# EQ_2.net
KiCad netlist of a schematic drawn in EAGLE
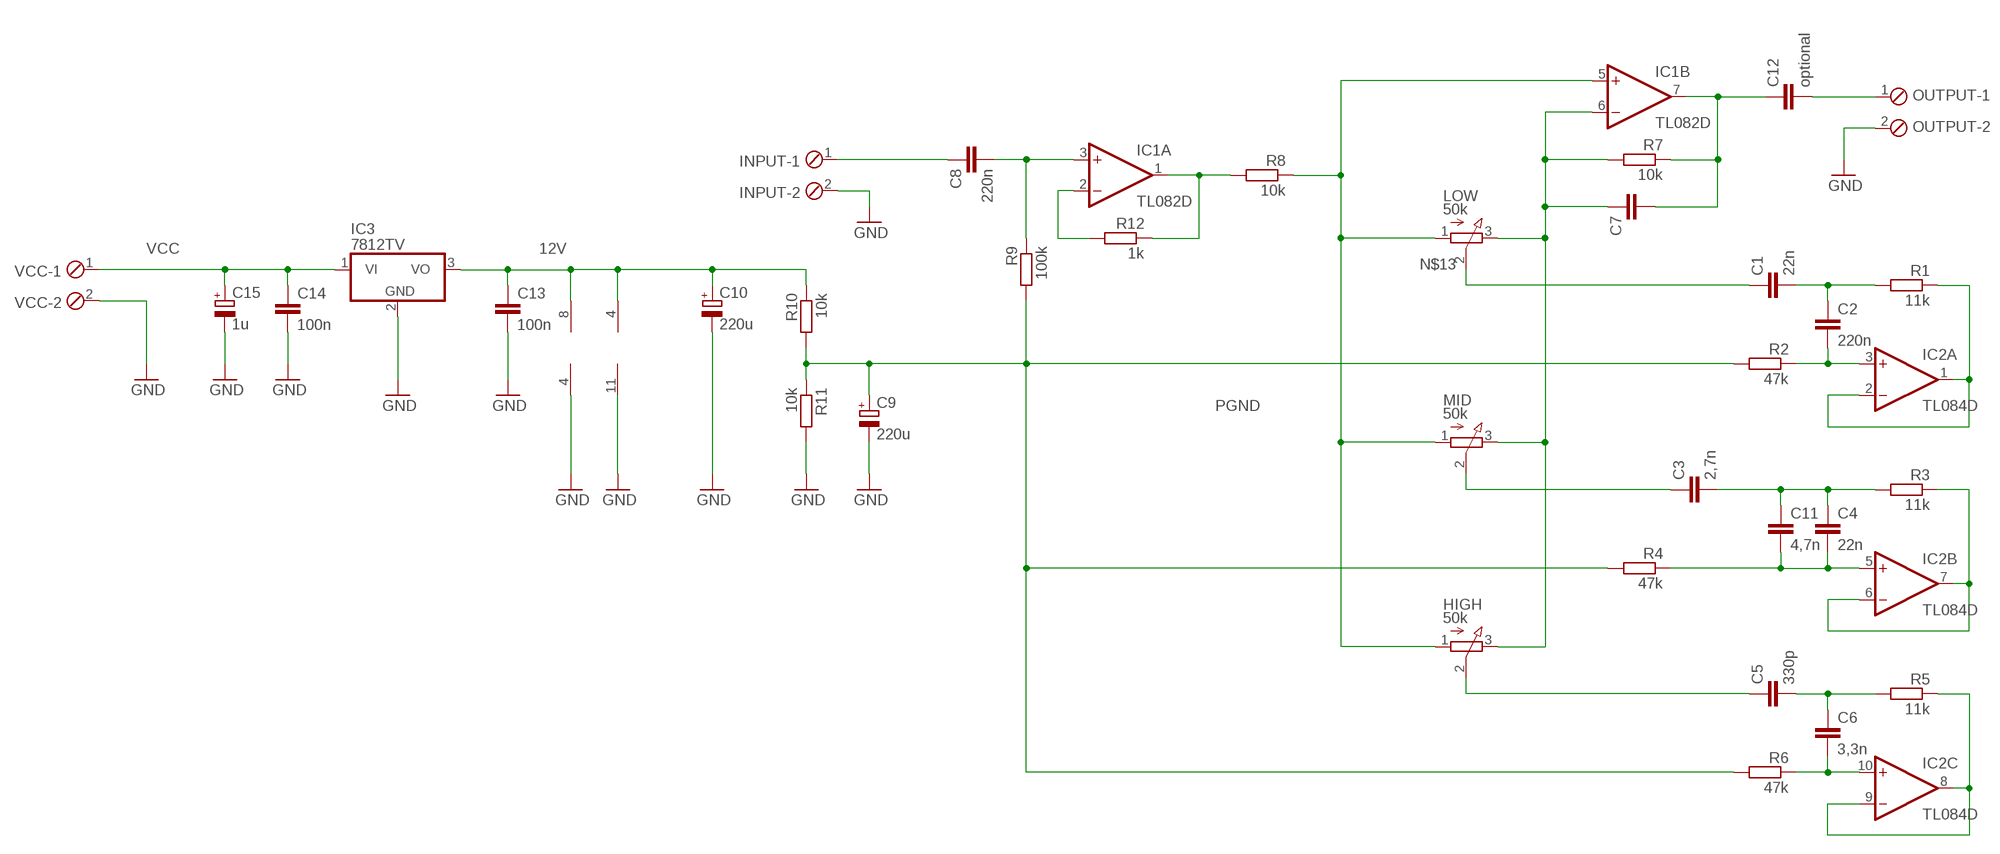
[diagram p0: schematic, sheet 1]

(export (version "E")
  (design (tool "Eeschema 10.0.6"))
  (components
    (comp (ref "C1")
      (value "22n")
      (footprint "eagle-import:C1206")
      (libsource (lib "eagle-import") (part "C-EUC1206"))
    )
    (comp (ref "C2")
      (value "220n")
      (footprint "eagle-import:C1206")
      (libsource (lib "eagle-import") (part "C-EUC1206"))
    )
    (comp (ref "C3")
      (value "2,7n")
      (footprint "eagle-import:C1206")
      (libsource (lib "eagle-import") (part "C-EUC1206"))
    )
    (comp (ref "C4")
      (value "22n")
      (footprint "eagle-import:C1206")
      (libsource (lib "eagle-import") (part "C-EUC1206"))
    )
    (comp (ref "C5")
      (value "330p")
      (footprint "eagle-import:C1206")
      (libsource (lib "eagle-import") (part "C-EUC1206"))
    )
    (comp (ref "C6")
      (value "3,3n")
      (footprint "eagle-import:C1206")
      (libsource (lib "eagle-import") (part "C-EUC1206"))
    )
    (comp (ref "C7")
      (value "C-EUC1206")
      (footprint "eagle-import:C1206")
      (libsource (lib "eagle-import") (part "C-EUC1206"))
    )
    (comp (ref "C8")
      (value "220n")
      (footprint "eagle-import:C1206")
      (libsource (lib "eagle-import") (part "C-EUC1206"))
    )
    (comp (ref "C9")
      (value "220u")
      (footprint "eagle-import:E2,5-5")
      (libsource (lib "eagle-import") (part "CPOL-EUE2.5-5"))
    )
    (comp (ref "C10")
      (value "220u")
      (footprint "eagle-import:E2,5-5")
      (libsource (lib "eagle-import") (part "CPOL-EUE2.5-5"))
    )
    (comp (ref "C11")
      (value "4,7n")
      (footprint "eagle-import:C1206")
      (libsource (lib "eagle-import") (part "C-EUC1206"))
    )
    (comp (ref "C12")
      (value "optional")
      (footprint "eagle-import:C1206")
      (libsource (lib "eagle-import") (part "C-EUC1206"))
    )
    (comp (ref "C13")
      (value "100n")
      (footprint "eagle-import:C1206")
      (libsource (lib "eagle-import") (part "C-EUC1206"))
    )
    (comp (ref "C14")
      (value "100n")
      (footprint "eagle-import:C1206")
      (libsource (lib "eagle-import") (part "C-EUC1206"))
    )
    (comp (ref "C15")
      (value "1u")
      (footprint "eagle-import:E2,5-5")
      (libsource (lib "eagle-import") (part "CPOL-EUE2.5-5"))
    )
    (comp (ref "HIGH")
      (value "50k")
      (footprint "eagle-import:3RP_1610N")
      (libsource (lib "eagle-import") (part "3RP/1610N"))
    )
    (comp (ref "IC1")
      (value "TL082D")
      (footprint "eagle-import:SO08")
      (libsource (lib "eagle-import") (part "TL082D"))
    )
    (comp (ref "IC2")
      (value "TL084D")
      (footprint "eagle-import:SO14")
      (libsource (lib "eagle-import") (part "TL084D"))
    )
    (comp (ref "IC3")
      (value "7812TV")
      (footprint "eagle-import:TO220V")
      (libsource (lib "eagle-import") (part "78TV12"))
    )
    (comp (ref "INPUT")
      (value "MPT2")
      (footprint "eagle-import:2POL254")
      (libsource (lib "eagle-import") (part "MPT2"))
    )
    (comp (ref "LOW")
      (value "50k")
      (footprint "eagle-import:3RP_1610N")
      (libsource (lib "eagle-import") (part "3RP/1610N"))
    )
    (comp (ref "MID")
      (value "50k")
      (footprint "eagle-import:3RP_1610N")
      (libsource (lib "eagle-import") (part "3RP/1610N"))
    )
    (comp (ref "OUTPUT")
      (value "MPT2")
      (footprint "eagle-import:2POL254")
      (libsource (lib "eagle-import") (part "MPT2"))
    )
    (comp (ref "R1")
      (value "11k")
      (footprint "eagle-import:R0805")
      (libsource (lib "eagle-import") (part "R-EU_R0805"))
    )
    (comp (ref "R2")
      (value "47k")
      (footprint "eagle-import:R0805")
      (libsource (lib "eagle-import") (part "R-EU_R0805"))
    )
    (comp (ref "R3")
      (value "11k")
      (footprint "eagle-import:R0805")
      (libsource (lib "eagle-import") (part "R-EU_R0805"))
    )
    (comp (ref "R4")
      (value "47k")
      (footprint "eagle-import:R0805")
      (libsource (lib "eagle-import") (part "R-EU_R0805"))
    )
    (comp (ref "R5")
      (value "11k")
      (footprint "eagle-import:R0805")
      (libsource (lib "eagle-import") (part "R-EU_R0805"))
    )
    (comp (ref "R6")
      (value "47k")
      (footprint "eagle-import:R0805")
      (libsource (lib "eagle-import") (part "R-EU_R0805"))
    )
    (comp (ref "R7")
      (value "10k")
      (footprint "eagle-import:R0805")
      (libsource (lib "eagle-import") (part "R-EU_R0805"))
    )
    (comp (ref "R8")
      (value "10k")
      (footprint "eagle-import:R0805")
      (libsource (lib "eagle-import") (part "R-EU_R0805"))
    )
    (comp (ref "R9")
      (value "100k")
      (footprint "eagle-import:R0805")
      (libsource (lib "eagle-import") (part "R-EU_R0805"))
    )
    (comp (ref "R10")
      (value "10k")
      (footprint "eagle-import:R0805")
      (libsource (lib "eagle-import") (part "R-EU_R0805"))
    )
    (comp (ref "R11")
      (value "10k")
      (footprint "eagle-import:R0805")
      (libsource (lib "eagle-import") (part "R-EU_R0805"))
    )
    (comp (ref "R12")
      (value "1k")
      (footprint "eagle-import:R0805")
      (libsource (lib "eagle-import") (part "R-EU_R0805"))
    )
    (comp (ref "VCC")
      (value "MPT2")
      (footprint "eagle-import:2POL254")
      (libsource (lib "eagle-import") (part "MPT2"))
    )
  )
  (nets
    (net (code "1") (name "/12V") (class "Default")
      (node (ref "C10") (pin "+") (pinfunction "+_+") (pintype "passive"))
      (node (ref "C13") (pin "1") (pinfunction "1_1") (pintype "passive"))
      (node (ref "IC1") (pin "8") (pinfunction "V+_8") (pintype "power_in"))
      (node (ref "IC2") (pin "4") (pinfunction "V+_4") (pintype "power_in"))
      (node (ref "IC3") (pin "3") (pinfunction "VO_3") (pintype "passive"))
      (node (ref "R10") (pin "1") (pinfunction "1_1") (pintype "passive"))
    )
    (net (code "2") (name "/N$13") (class "Default")
      (node (ref "HIGH") (pin "1") (pinfunction "A_1") (pintype "passive"))
      (node (ref "IC1") (pin "5") (pinfunction "+IN_5") (pintype "input"))
      (node (ref "LOW") (pin "1") (pinfunction "A_1") (pintype "passive"))
      (node (ref "MID") (pin "1") (pinfunction "A_1") (pintype "passive"))
      (node (ref "R8") (pin "1") (pinfunction "1_1") (pintype "passive"))
    )
    (net (code "3") (name "/PGND") (class "Default")
      (node (ref "C9") (pin "+") (pinfunction "+_+") (pintype "passive"))
      (node (ref "R10") (pin "2") (pinfunction "2_2") (pintype "passive"))
      (node (ref "R11") (pin "1") (pinfunction "1_1") (pintype "passive"))
      (node (ref "R2") (pin "2") (pinfunction "2_2") (pintype "passive"))
      (node (ref "R4") (pin "2") (pinfunction "2_2") (pintype "passive"))
      (node (ref "R6") (pin "2") (pinfunction "2_2") (pintype "passive"))
      (node (ref "R9") (pin "2") (pinfunction "2_2") (pintype "passive"))
    )
    (net (code "4") (name "/VCC") (class "Default")
      (node (ref "C14") (pin "1") (pinfunction "1_1") (pintype "passive"))
      (node (ref "C15") (pin "+") (pinfunction "+_+") (pintype "passive"))
      (node (ref "IC3") (pin "1") (pinfunction "VI_1") (pintype "input"))
      (node (ref "VCC") (pin "1") (pinfunction "1_1") (pintype "passive"))
    )
    (net (code "5") (name "GND") (class "Default")
      (node (ref "C10") (pin "-") (pinfunction "-_-") (pintype "passive"))
      (node (ref "C13") (pin "2") (pinfunction "2_2") (pintype "passive"))
      (node (ref "C14") (pin "2") (pinfunction "2_2") (pintype "passive"))
      (node (ref "C15") (pin "-") (pinfunction "-_-") (pintype "passive"))
      (node (ref "C9") (pin "-") (pinfunction "-_-") (pintype "passive"))
      (node (ref "IC1") (pin "4") (pinfunction "V-_4") (pintype "power_in"))
      (node (ref "IC2") (pin "11") (pinfunction "V-_11") (pintype "power_in"))
      (node (ref "IC3") (pin "2") (pinfunction "GND_2") (pintype "passive"))
      (node (ref "INPUT") (pin "2") (pinfunction "1_2") (pintype "passive"))
      (node (ref "OUTPUT") (pin "2") (pinfunction "1_2") (pintype "passive"))
      (node (ref "R11") (pin "2") (pinfunction "2_2") (pintype "passive"))
      (node (ref "VCC") (pin "2") (pinfunction "1_2") (pintype "passive"))
    )
    (net (code "6") (name "Net-(C1-Pad2)") (class "Default")
      (node (ref "C1") (pin "2") (pinfunction "2_2") (pintype "passive"))
      (node (ref "C2") (pin "1") (pinfunction "1_1") (pintype "passive"))
      (node (ref "R1") (pin "2") (pinfunction "2_2") (pintype "passive"))
    )
    (net (code "7") (name "Net-(C5-Pad2)") (class "Default")
      (node (ref "C5") (pin "2") (pinfunction "2_2") (pintype "passive"))
      (node (ref "C6") (pin "1") (pinfunction "1_1") (pintype "passive"))
      (node (ref "R5") (pin "2") (pinfunction "2_2") (pintype "passive"))
    )
    (net (code "8") (name "Net-(C8-Pad1)") (class "Default")
      (node (ref "C8") (pin "1") (pinfunction "1_1") (pintype "passive"))
      (node (ref "INPUT") (pin "1") (pinfunction "1_1") (pintype "passive"))
    )
    (net (code "9") (name "Net-(C11-Pad1)") (class "Default")
      (node (ref "C11") (pin "1") (pinfunction "1_1") (pintype "passive"))
      (node (ref "C3") (pin "2") (pinfunction "2_2") (pintype "passive"))
      (node (ref "C4") (pin "1") (pinfunction "1_1") (pintype "passive"))
      (node (ref "R3") (pin "2") (pinfunction "2_2") (pintype "passive"))
    )
    (net (code "10") (name "Net-(C12-Pad2)") (class "Default")
      (node (ref "C12") (pin "2") (pinfunction "2_2") (pintype "passive"))
      (node (ref "OUTPUT") (pin "1") (pinfunction "1_1") (pintype "passive"))
    )
    (net (code "11") (name "Net-(HIGH-E)") (class "Default")
      (node (ref "C7") (pin "1") (pinfunction "1_1") (pintype "passive"))
      (node (ref "HIGH") (pin "3") (pinfunction "E_3") (pintype "passive"))
      (node (ref "IC1") (pin "6") (pinfunction "-IN_6") (pintype "input"))
      (node (ref "LOW") (pin "3") (pinfunction "E_3") (pintype "passive"))
      (node (ref "MID") (pin "3") (pinfunction "E_3") (pintype "passive"))
      (node (ref "R7") (pin "2") (pinfunction "2_2") (pintype "passive"))
    )
    (net (code "12") (name "Net-(HIGH-S)") (class "Default")
      (node (ref "C5") (pin "1") (pinfunction "1_1") (pintype "passive"))
      (node (ref "HIGH") (pin "2") (pinfunction "S_2") (pintype "passive"))
    )
    (net (code "13") (name "Net-(IC1A-+IN)") (class "Default")
      (node (ref "C8") (pin "2") (pinfunction "2_2") (pintype "passive"))
      (node (ref "IC1") (pin "3") (pinfunction "+IN_3") (pintype "input"))
      (node (ref "R9") (pin "1") (pinfunction "1_1") (pintype "passive"))
    )
    (net (code "14") (name "Net-(IC1A--IN)") (class "Default")
      (node (ref "IC1") (pin "2") (pinfunction "-IN_2") (pintype "input"))
      (node (ref "R12") (pin "2") (pinfunction "2_2") (pintype "passive"))
    )
    (net (code "15") (name "Net-(IC1A-OUT)") (class "Default")
      (node (ref "IC1") (pin "1") (pinfunction "OUT_1") (pintype "output"))
      (node (ref "R12") (pin "1") (pinfunction "1_1") (pintype "passive"))
      (node (ref "R8") (pin "2") (pinfunction "2_2") (pintype "passive"))
    )
    (net (code "16") (name "Net-(IC1B-OUT)") (class "Default")
      (node (ref "C12") (pin "1") (pinfunction "1_1") (pintype "passive"))
      (node (ref "C7") (pin "2") (pinfunction "2_2") (pintype "passive"))
      (node (ref "IC1") (pin "7") (pinfunction "OUT_7") (pintype "output"))
      (node (ref "R7") (pin "1") (pinfunction "1_1") (pintype "passive"))
    )
    (net (code "17") (name "Net-(IC2A-+IN)") (class "Default")
      (node (ref "C2") (pin "2") (pinfunction "2_2") (pintype "passive"))
      (node (ref "IC2") (pin "3") (pinfunction "+IN_3") (pintype "input"))
      (node (ref "R2") (pin "1") (pinfunction "1_1") (pintype "passive"))
    )
    (net (code "18") (name "Net-(IC2A--IN)") (class "Default")
      (node (ref "IC2") (pin "1") (pinfunction "OUT_1") (pintype "output"))
      (node (ref "IC2") (pin "2") (pinfunction "-IN_2") (pintype "input"))
      (node (ref "R1") (pin "1") (pinfunction "1_1") (pintype "passive"))
    )
    (net (code "19") (name "Net-(IC2B-+IN)") (class "Default")
      (node (ref "C11") (pin "2") (pinfunction "2_2") (pintype "passive"))
      (node (ref "C4") (pin "2") (pinfunction "2_2") (pintype "passive"))
      (node (ref "IC2") (pin "5") (pinfunction "+IN_5") (pintype "input"))
      (node (ref "R4") (pin "1") (pinfunction "1_1") (pintype "passive"))
    )
    (net (code "20") (name "Net-(IC2B--IN)") (class "Default")
      (node (ref "IC2") (pin "6") (pinfunction "-IN_6") (pintype "input"))
      (node (ref "IC2") (pin "7") (pinfunction "OUT_7") (pintype "output"))
      (node (ref "R3") (pin "1") (pinfunction "1_1") (pintype "passive"))
    )
    (net (code "21") (name "Net-(IC2C-+IN)") (class "Default")
      (node (ref "C6") (pin "2") (pinfunction "2_2") (pintype "passive"))
      (node (ref "IC2") (pin "10") (pinfunction "+IN_10") (pintype "input"))
      (node (ref "R6") (pin "1") (pinfunction "1_1") (pintype "passive"))
    )
    (net (code "22") (name "Net-(IC2C--IN)") (class "Default")
      (node (ref "IC2") (pin "8") (pinfunction "OUT_8") (pintype "output"))
      (node (ref "IC2") (pin "9") (pinfunction "-IN_9") (pintype "input"))
      (node (ref "R5") (pin "1") (pinfunction "1_1") (pintype "passive"))
    )
    (net (code "23") (name "Net-(LOW-S)") (class "Default")
      (node (ref "C1") (pin "1") (pinfunction "1_1") (pintype "passive"))
      (node (ref "LOW") (pin "2") (pinfunction "S_2") (pintype "passive"))
    )
    (net (code "24") (name "Net-(MID-S)") (class "Default")
      (node (ref "C3") (pin "1") (pinfunction "1_1") (pintype "passive"))
      (node (ref "MID") (pin "2") (pinfunction "S_2") (pintype "passive"))
    )
  )
)
